# FDCAN.net
KiCad netlist of a schematic drawn in Altium Designer
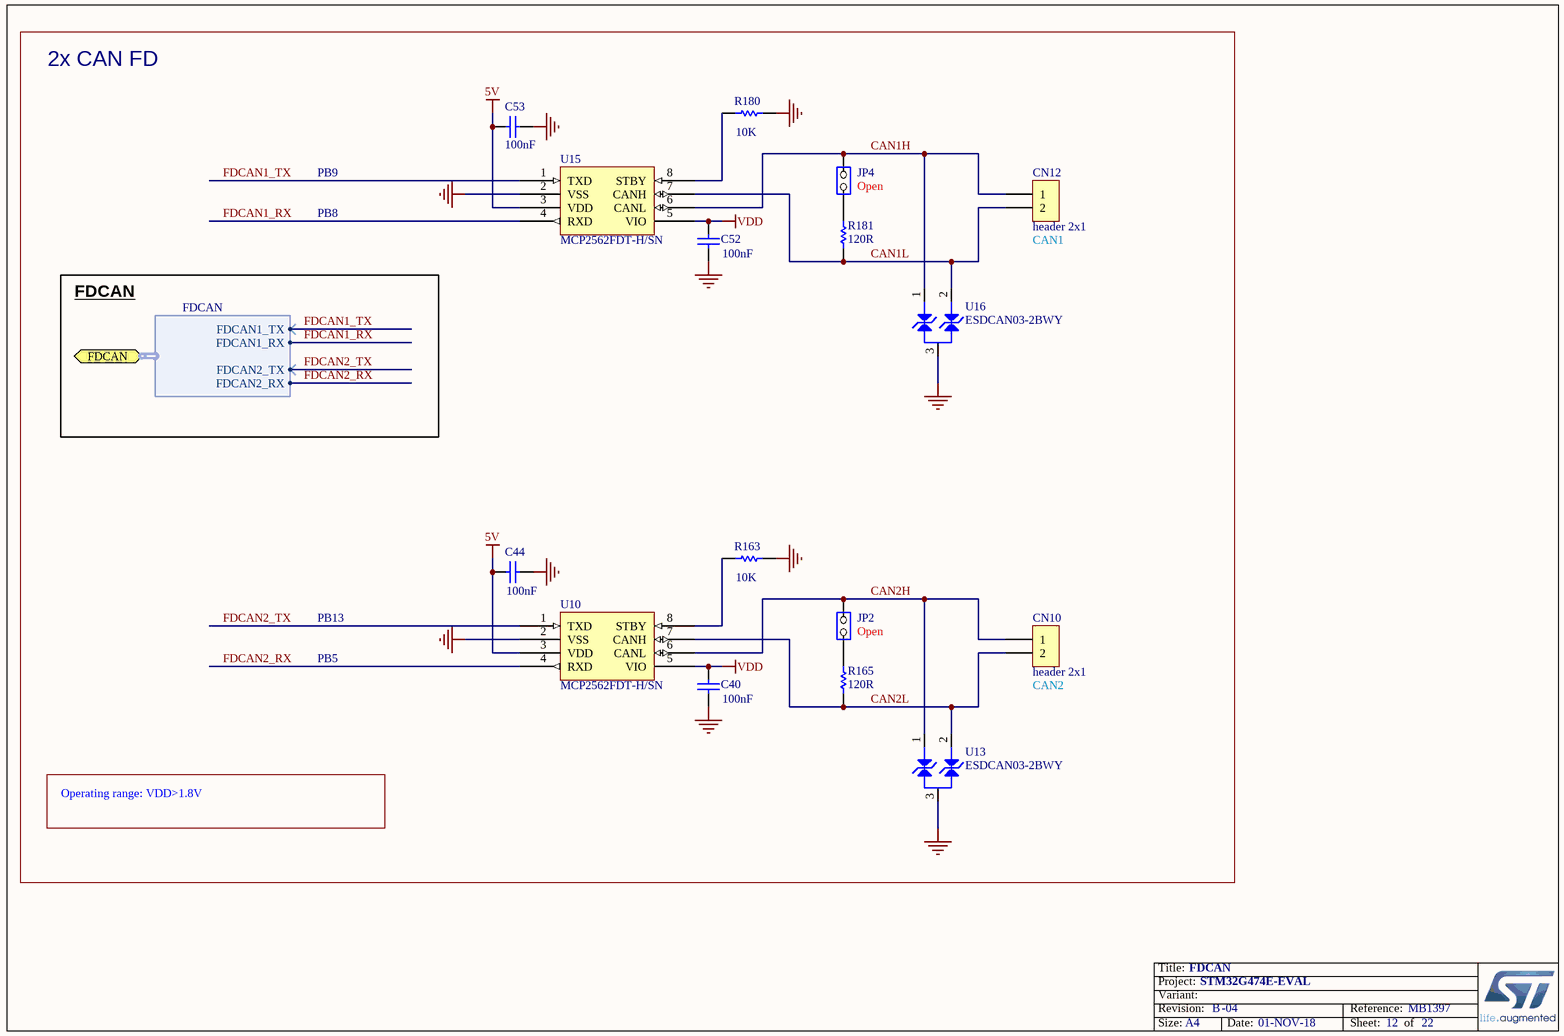
[diagram p0: FDCAN.SchDoc]

(export (version "E")
  (design (tool "Eeschema 10.0.6"))
  (components
    (comp (ref "C40")
      (value "100nF")
      (footprint "C0402")
      (description "Capacitor, MLCC, 100nF, 16V, X7R, 10%, 0402, T=0.5mm")
      (fields
        (field (name "INTERNAL_PART_NUMBER") "MCD-00006")
        (field (name "MANUFACTURER_PART_NUMBER") "CC0402KRX7R7BB104")
        (field (name "PROVIDED_BY") "SUBCO")
      )
      (libsource (lib "MCD_PARTS_database") (part "Capacitor"))
    )
    (comp (ref "C44")
      (value "100nF")
      (footprint "C0402")
      (description "Capacitor, MLCC, 100nF, 16V, X7R, 10%, 0402, T=0.5mm")
      (fields
        (field (name "INTERNAL_PART_NUMBER") "MCD-00006")
        (field (name "MANUFACTURER_PART_NUMBER") "CC0402KRX7R7BB104")
        (field (name "PROVIDED_BY") "SUBCO")
      )
      (libsource (lib "MCD_PARTS_database") (part "Capacitor"))
    )
    (comp (ref "C52")
      (value "100nF")
      (footprint "C0402")
      (description "Capacitor, MLCC, 100nF, 16V, X7R, 10%, 0402, T=0.5mm")
      (fields
        (field (name "INTERNAL_PART_NUMBER") "MCD-00006")
        (field (name "MANUFACTURER_PART_NUMBER") "CC0402KRX7R7BB104")
        (field (name "PROVIDED_BY") "SUBCO")
      )
      (libsource (lib "MCD_PARTS_database") (part "Capacitor"))
    )
    (comp (ref "C53")
      (value "100nF")
      (footprint "C0402")
      (description "Capacitor, MLCC, 100nF, 16V, X7R, 10%, 0402, T=0.5mm")
      (fields
        (field (name "INTERNAL_PART_NUMBER") "MCD-00006")
        (field (name "MANUFACTURER_PART_NUMBER") "CC0402KRX7R7BB104")
        (field (name "PROVIDED_BY") "SUBCO")
      )
      (libsource (lib "MCD_PARTS_database") (part "Capacitor"))
    )
    (comp (ref "CN10")
      (value "header 2x1")
      (footprint "CON_988-JIUBABA_PHFS25-11-02-G0B115-T-1")
      (description "Header, 2x1, 2.54mm, VR, TH, Height 6mm/3mm")
      (fields
        (field (name "INTERNAL_PART_NUMBER") "MCD-00314")
        (field (name "MANUFACTURER_PART_NUMBER") "PHFS25-11-02-G0B115-T-1")
        (field (name "PROVIDED_BY") "SUBCO")
      )
      (libsource (lib "MCD_PARTS_database") (part "Header 2x1"))
    )
    (comp (ref "CN12")
      (value "header 2x1")
      (footprint "CON_988-JIUBABA_PHFS25-11-02-G0B115-T-1")
      (description "Header, 2x1, 2.54mm, VR, TH, Height 6mm/3mm")
      (fields
        (field (name "INTERNAL_PART_NUMBER") "MCD-00314")
        (field (name "MANUFACTURER_PART_NUMBER") "PHFS25-11-02-G0B115-T-1")
        (field (name "PROVIDED_BY") "SUBCO")
      )
      (libsource (lib "MCD_PARTS_database") (part "Header 2x1"))
    )
    (comp (ref "JP2")
      (value "Jumper_Header 2x1")
      (footprint "CON_SAMTEC_TSW-102-07-G-S")
      (description "Header, 2x1, 2,54mm, VR, TH, Height 5.84mm/2.54mm")
      (fields
        (field (name "INTERNAL_PART_NUMBER") "MCD-00045")
        (field (name "MANUFACTURER_PART_NUMBER") "TSW-102-07-x-S")
        (field (name "PROVIDED_BY") "SUBCO")
      )
      (libsource (lib "MCD_PARTS_database") (part "Jumper_Header 2x1"))
    )
    (comp (ref "JP4")
      (value "Jumper_Header 2x1")
      (footprint "CON_SAMTEC_TSW-102-07-G-S")
      (description "Header, 2x1, 2,54mm, VR, TH, Height 5.84mm/2.54mm")
      (fields
        (field (name "INTERNAL_PART_NUMBER") "MCD-00045")
        (field (name "MANUFACTURER_PART_NUMBER") "TSW-102-07-x-S")
        (field (name "PROVIDED_BY") "SUBCO")
      )
      (libsource (lib "MCD_PARTS_database") (part "Jumper_Header 2x1"))
    )
    (comp (ref "R163")
      (value "10K")
      (footprint "R0402")
      (description "Resistor,10K,0402,1%,1/16W")
      (fields
        (field (name "INTERNAL_PART_NUMBER") "MCD-00053")
        (field (name "MANUFACTURER_PART_NUMBER") "RC0402FR-0710KL")
        (field (name "PROVIDED_BY") "SUBCO")
      )
      (libsource (lib "MCD_PARTS_database") (part "Resistor"))
    )
    (comp (ref "R165")
      (value "120R")
      (footprint "R0603")
      (description "Resistor,120R,0603,1%,1/10W")
      (fields
        (field (name "INTERNAL_PART_NUMBER") "MCD-00338")
        (field (name "MANUFACTURER_PART_NUMBER") "RC0603FR-07120RL")
        (field (name "PROVIDED_BY") "SUBCO")
      )
      (libsource (lib "MCD_PARTS_database") (part "Resistor"))
    )
    (comp (ref "R180")
      (value "10K")
      (footprint "R0402")
      (description "Resistor,10K,0402,1%,1/16W")
      (fields
        (field (name "INTERNAL_PART_NUMBER") "MCD-00053")
        (field (name "MANUFACTURER_PART_NUMBER") "RC0402FR-0710KL")
        (field (name "PROVIDED_BY") "SUBCO")
      )
      (libsource (lib "MCD_PARTS_database") (part "Resistor"))
    )
    (comp (ref "R181")
      (value "120R")
      (footprint "R0603")
      (description "Resistor,120R,0603,1%,1/10W")
      (fields
        (field (name "INTERNAL_PART_NUMBER") "MCD-00338")
        (field (name "MANUFACTURER_PART_NUMBER") "RC0603FR-07120RL")
        (field (name "PROVIDED_BY") "SUBCO")
      )
      (libsource (lib "MCD_PARTS_database") (part "Resistor"))
    )
    (comp (ref "U10")
      (value "MCP2562FDT-H/SN")
      (footprint "ICC_SO8_5X4_P127")
      (description "High-Speed CAN Flexible Data Rate Transceiver")
      (fields
        (field (name "INTERNAL_PART_NUMBER") "MCD-00129")
        (field (name "MANUFACTURER") "MICROCHIP")
        (field (name "PROVIDED_BY") "SUBCO")
      )
      (libsource (lib "MCD_PARTS_database") (part "MCP2562FD"))
    )
    (comp (ref "U13")
      (value "ESDCAN03-2BWY")
      (footprint "DIO_SOT323")
      (fields
        (field (name "INTERNAL_PART_NUMBER") "MCD-01228")
        (field (name "MANUFACTURER") "STMICROELECTRONICS")
        (field (name "Comment") "ESD-TRANSIL-DUAL-BIDIR")
        (field (name "PROVIDED_BY") "SUBCO with ST control")
      )
      (libsource (lib "MCD_PARTS_database") (part "ESD-TRANSIL-DUAL-BIDIR"))
    )
    (comp (ref "U15")
      (value "MCP2562FDT-H/SN")
      (footprint "ICC_SO8_5X4_P127")
      (description "High-Speed CAN Flexible Data Rate Transceiver")
      (fields
        (field (name "INTERNAL_PART_NUMBER") "MCD-00129")
        (field (name "MANUFACTURER") "MICROCHIP")
        (field (name "PROVIDED_BY") "SUBCO")
      )
      (libsource (lib "MCD_PARTS_database") (part "MCP2562FD"))
    )
    (comp (ref "U16")
      (value "ESDCAN03-2BWY")
      (footprint "DIO_SOT323")
      (fields
        (field (name "INTERNAL_PART_NUMBER") "MCD-01228")
        (field (name "MANUFACTURER") "STMICROELECTRONICS")
        (field (name "Comment") "ESD-TRANSIL-DUAL-BIDIR")
        (field (name "PROVIDED_BY") "SUBCO with ST control")
      )
      (libsource (lib "MCD_PARTS_database") (part "ESD-TRANSIL-DUAL-BIDIR"))
    )
  )
  (nets
    (net (code "2") (name "/CAN1H") (class "Default")
      (node (ref "CN12") (pin "1") (pinfunction "1_1") (pintype "passive"))
      (node (ref "JP4") (pin "2") (pinfunction "NO_2") (pintype "passive"))
      (node (ref "U15") (pin "6") (pinfunction "CANL_6") (pintype "bidirectional"))
      (node (ref "U16") (pin "1") (pintype "passive"))
    )
    (net (code "3") (name "/CAN1L") (class "Default")
      (node (ref "CN12") (pin "2") (pinfunction "2_2") (pintype "passive"))
      (node (ref "R181") (pin "1") (pinfunction "1_1") (pintype "passive"))
      (node (ref "U15") (pin "7") (pinfunction "CANH_7") (pintype "bidirectional"))
      (node (ref "U16") (pin "2") (pintype "passive"))
    )
    (net (code "4") (name "/CAN2H") (class "Default")
      (node (ref "CN10") (pin "1") (pinfunction "1_1") (pintype "passive"))
      (node (ref "JP2") (pin "2") (pinfunction "NO_2") (pintype "passive"))
      (node (ref "U10") (pin "6") (pinfunction "CANL_6") (pintype "bidirectional"))
      (node (ref "U13") (pin "1") (pintype "passive"))
    )
    (net (code "5") (name "/CAN2L") (class "Default")
      (node (ref "CN10") (pin "2") (pinfunction "2_2") (pintype "passive"))
      (node (ref "R165") (pin "1") (pinfunction "1_1") (pintype "passive"))
      (node (ref "U10") (pin "7") (pinfunction "CANH_7") (pintype "bidirectional"))
      (node (ref "U13") (pin "2") (pintype "passive"))
    )
    (net (code "6") (name "/FDCAN1_RX") (class "Default")
      (node (ref "U15") (pin "4") (pinfunction "RXD_4") (pintype "output"))
    )
    (net (code "7") (name "/FDCAN1_TX") (class "Default")
      (node (ref "U15") (pin "1") (pinfunction "TXD_1") (pintype "input"))
    )
    (net (code "8") (name "/FDCAN2_RX") (class "Default")
      (node (ref "U10") (pin "4") (pinfunction "RXD_4") (pintype "output"))
    )
    (net (code "9") (name "/FDCAN2_TX") (class "Default")
      (node (ref "U10") (pin "1") (pinfunction "TXD_1") (pintype "input"))
    )
    (net (code "11") (name "5V") (class "Default")
      (node (ref "C44") (pin "1") (pinfunction "1_1") (pintype "passive"))
      (node (ref "C53") (pin "1") (pinfunction "1_1") (pintype "passive"))
      (node (ref "U10") (pin "3") (pinfunction "VDD_3") (pintype "power_in"))
      (node (ref "U15") (pin "3") (pinfunction "VDD_3") (pintype "power_in"))
    )
    (net (code "12") (name "GND") (class "Default")
      (node (ref "C40") (pin "2") (pinfunction "2_2") (pintype "passive"))
      (node (ref "C44") (pin "2") (pinfunction "2_2") (pintype "passive"))
      (node (ref "C52") (pin "2") (pinfunction "2_2") (pintype "passive"))
      (node (ref "C53") (pin "2") (pinfunction "2_2") (pintype "passive"))
      (node (ref "R163") (pin "2") (pinfunction "2_2") (pintype "passive"))
      (node (ref "R180") (pin "2") (pinfunction "2_2") (pintype "passive"))
      (node (ref "U10") (pin "2") (pinfunction "VSS_2") (pintype "power_in"))
      (node (ref "U13") (pin "3") (pintype "passive"))
      (node (ref "U15") (pin "2") (pinfunction "VSS_2") (pintype "power_in"))
      (node (ref "U16") (pin "3") (pintype "passive"))
    )
    (net (code "13") (name "Net-(JP2-COMMON)") (class "Default")
      (node (ref "JP2") (pin "1") (pinfunction "COMMON_1") (pintype "passive"))
      (node (ref "R165") (pin "2") (pinfunction "2_2") (pintype "passive"))
    )
    (net (code "14") (name "Net-(JP4-COMMON)") (class "Default")
      (node (ref "JP4") (pin "1") (pinfunction "COMMON_1") (pintype "passive"))
      (node (ref "R181") (pin "2") (pinfunction "2_2") (pintype "passive"))
    )
    (net (code "15") (name "Net-(U10-STBY)") (class "Default")
      (node (ref "R163") (pin "1") (pinfunction "1_1") (pintype "passive"))
      (node (ref "U10") (pin "8") (pinfunction "STBY_8") (pintype "input"))
    )
    (net (code "16") (name "Net-(U15-STBY)") (class "Default")
      (node (ref "R180") (pin "1") (pinfunction "1_1") (pintype "passive"))
      (node (ref "U15") (pin "8") (pinfunction "STBY_8") (pintype "input"))
    )
    (net (code "17") (name "VDD") (class "Default")
      (node (ref "C40") (pin "1") (pinfunction "1_1") (pintype "passive"))
      (node (ref "C52") (pin "1") (pinfunction "1_1") (pintype "passive"))
      (node (ref "U10") (pin "5") (pinfunction "VIO_5") (pintype "power_in"))
      (node (ref "U15") (pin "5") (pinfunction "VIO_5") (pintype "power_in"))
    )
  )
)
